# Clocks.net
KiCad netlist of a schematic drawn in Altium Designer
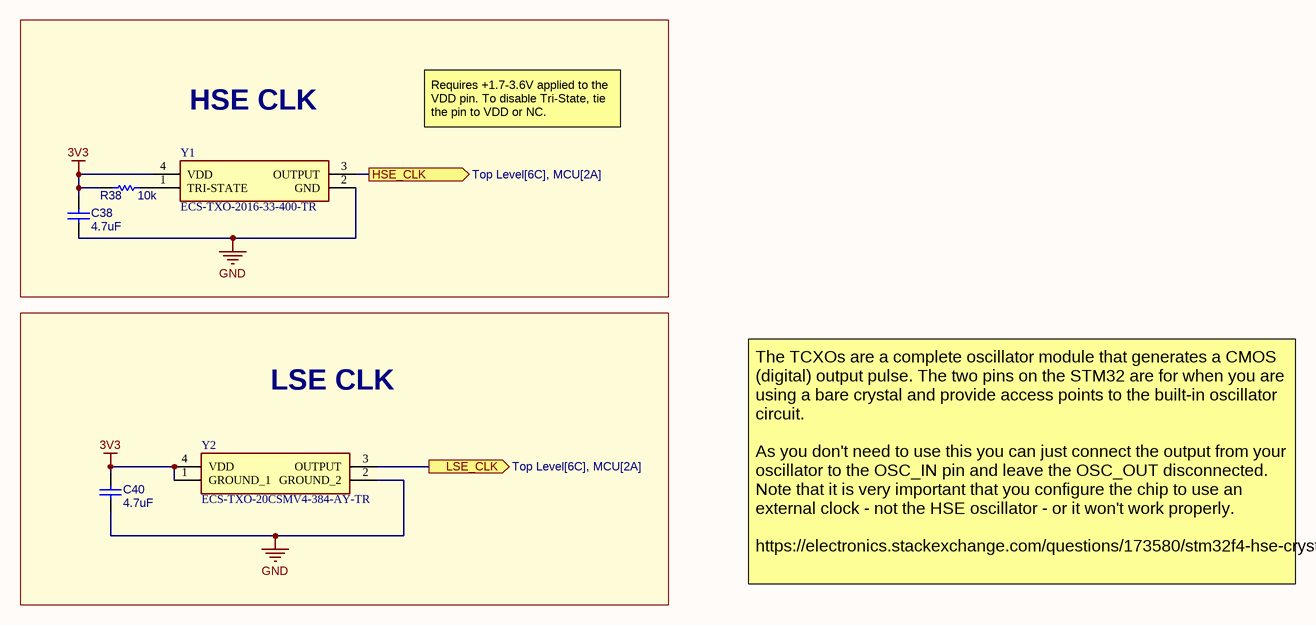
[diagram p0: Clocks.SchDoc]

(export (version "E")
  (design (tool "Eeschema 10.0.6"))
  (components
    (comp (ref "C38")
      (value "4.7uF")
      (footprint "C0603")
      (description "Capacitor, MLCC, 100nF, 6V3, X5R, 10%, 0603, T=0,8mm")
      (fields
        (field (name "MANUFACTURER PART NUMBER") "CC0603KRX5R5BB104")
        (field (name "MANUFACTURER") "YAGEO")
        (field (name "PROVIDED_BY") "SUBCO")
      )
      (libsource (lib "Perth Aerospace Student Team") (part "CMP-035-000015-1"))
    )
    (comp (ref "C40")
      (value "4.7uF")
      (footprint "C0603")
      (description "Capacitor, MLCC, 100nF, 6V3, X5R, 10%, 0603, T=0,8mm")
      (fields
        (field (name "MANUFACTURER PART NUMBER") "CC0603KRX5R5BB104")
        (field (name "MANUFACTURER") "YAGEO")
        (field (name "PROVIDED_BY") "SUBCO")
      )
      (libsource (lib "Perth Aerospace Student Team") (part "CMP-035-000015-1"))
    )
    (comp (ref "R38")
      (value "10k")
      (footprint "RESC1608X55X25ML10T15-1")
      (description "Chip Resistor, 10k Ohm, 0.1 W, -55 to 155 degC, 0603 (1608 Metric)")
      (fields
        (field (name "POWER") "100mW")
        (field (name "TOLERANCE") "1%")
        (field (name "CREATED BY") "Micah Randall")
      )
      (libsource (lib "Perth Aerospace Student Team") (part "CMP-009-00006-5"))
    )
    (comp (ref "Y1")
      (value "ECS-TXO-2016-33-400-TR")
      (footprint "C2Sv0 - Processor:ECS-TXO-2016-33-400-TR")
      (description "Crystal or Oscillator")
      (fields (field (name "MOUSER PART NUMBER") "520-TXO-2016-33-400T"))
      (libsource (lib "C2Sv0 - Processor") (part "ECS-TXO-2016-33-400-TR"))
    )
    (comp (ref "Y2")
      (value "ECS-TXO-20CSMV4-384-AY-TR")
      (footprint "C2Sv0 - Processor:ECS-TXO-20CSMV4-384-AY-TR")
      (description "Crystal or Oscillator")
      (libsource (lib "C2Sv0 - Processor") (part "ECS-TXO-20CSMV4-384-AY-TR"))
    )
  )
  (nets
    (net (code "1") (name "/HSE_CLK") (class "Default")
      (node (ref "Y1") (pin "3") (pinfunction "OUTPUT_3") (pintype "passive"))
    )
    (net (code "2") (name "/LSE_CLK") (class "Default")
      (node (ref "Y2") (pin "3") (pinfunction "OUTPUT_3") (pintype "passive"))
    )
    (net (code "3") (name "3V3") (class "Default")
      (node (ref "C38") (pin "2") (pinfunction "2_2") (pintype "passive"))
      (node (ref "C40") (pin "1") (pinfunction "1_1") (pintype "passive"))
      (node (ref "R38") (pin "1") (pinfunction "1_1") (pintype "passive"))
      (node (ref "Y1") (pin "4") (pinfunction "VDD_4") (pintype "passive"))
      (node (ref "Y2") (pin "1") (pinfunction "GROUND_1_1") (pintype "passive"))
      (node (ref "Y2") (pin "4") (pinfunction "VDD_4") (pintype "passive"))
    )
    (net (code "4") (name "GND") (class "Default")
      (node (ref "C38") (pin "1") (pinfunction "1_1") (pintype "passive"))
      (node (ref "C40") (pin "2") (pinfunction "2_2") (pintype "passive"))
      (node (ref "Y1") (pin "2") (pinfunction "GND_2") (pintype "passive"))
      (node (ref "Y2") (pin "2") (pinfunction "GROUND_2_2") (pintype "passive"))
    )
    (net (code "5") (name "Net-(Y1-TRI-STATE)") (class "Default")
      (node (ref "R38") (pin "2") (pinfunction "2_2") (pintype "passive"))
      (node (ref "Y1") (pin "1") (pinfunction "TRI-STATE_1") (pintype "passive"))
    )
  )
)
